# PwrSplit.net
KiCad netlist of a schematic drawn in EAGLE
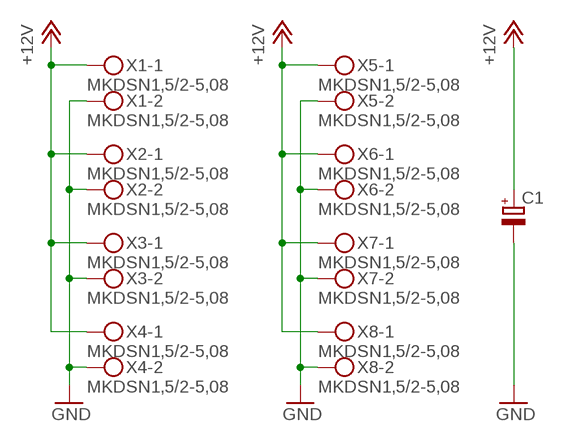
[diagram p0: schematic, sheet 1]

(export (version "E")
  (design (tool "Eeschema 10.0.6"))
  (components
    (comp (ref "C1")
      (value "ECAP")
      (footprint "eagle-import:E5-13")
      (libsource (lib "eagle-import") (part "ECAP"))
    )
    (comp (ref "X1")
      (value "MKDSN1,5/2-5,08")
      (footprint "eagle-import:MKDSN1,5_2-5,08")
      (libsource (lib "eagle-import") (part "MKDSN1,5/2-5,08"))
    )
    (comp (ref "X2")
      (value "MKDSN1,5/2-5,08")
      (footprint "eagle-import:MKDSN1,5_2-5,08")
      (libsource (lib "eagle-import") (part "MKDSN1,5/2-5,08"))
    )
    (comp (ref "X3")
      (value "MKDSN1,5/2-5,08")
      (footprint "eagle-import:MKDSN1,5_2-5,08")
      (libsource (lib "eagle-import") (part "MKDSN1,5/2-5,08"))
    )
    (comp (ref "X4")
      (value "MKDSN1,5/2-5,08")
      (footprint "eagle-import:MKDSN1,5_2-5,08")
      (libsource (lib "eagle-import") (part "MKDSN1,5/2-5,08"))
    )
    (comp (ref "X5")
      (value "MKDSN1,5/2-5,08")
      (footprint "eagle-import:MKDSN1,5_2-5,08")
      (libsource (lib "eagle-import") (part "MKDSN1,5/2-5,08"))
    )
    (comp (ref "X6")
      (value "MKDSN1,5/2-5,08")
      (footprint "eagle-import:MKDSN1,5_2-5,08")
      (libsource (lib "eagle-import") (part "MKDSN1,5/2-5,08"))
    )
    (comp (ref "X7")
      (value "MKDSN1,5/2-5,08")
      (footprint "eagle-import:MKDSN1,5_2-5,08")
      (libsource (lib "eagle-import") (part "MKDSN1,5/2-5,08"))
    )
    (comp (ref "X8")
      (value "MKDSN1,5/2-5,08")
      (footprint "eagle-import:MKDSN1,5_2-5,08")
      (libsource (lib "eagle-import") (part "MKDSN1,5/2-5,08"))
    )
  )
  (nets
    (net (code "1") (name "+12V") (class "Default")
      (node (ref "C1") (pin "+") (pinfunction "+_+") (pintype "passive"))
      (node (ref "X1") (pin "1") (pinfunction "KL_1") (pintype "passive"))
      (node (ref "X2") (pin "1") (pinfunction "KL_1") (pintype "passive"))
      (node (ref "X3") (pin "1") (pinfunction "KL_1") (pintype "passive"))
      (node (ref "X4") (pin "1") (pinfunction "KL_1") (pintype "passive"))
      (node (ref "X5") (pin "1") (pinfunction "KL_1") (pintype "passive"))
      (node (ref "X6") (pin "1") (pinfunction "KL_1") (pintype "passive"))
      (node (ref "X7") (pin "1") (pinfunction "KL_1") (pintype "passive"))
      (node (ref "X8") (pin "1") (pinfunction "KL_1") (pintype "passive"))
    )
    (net (code "2") (name "GND") (class "Default")
      (node (ref "C1") (pin "-") (pinfunction "-_-") (pintype "passive"))
      (node (ref "X1") (pin "2") (pinfunction "KL_2") (pintype "passive"))
      (node (ref "X2") (pin "2") (pinfunction "KL_2") (pintype "passive"))
      (node (ref "X3") (pin "2") (pinfunction "KL_2") (pintype "passive"))
      (node (ref "X4") (pin "2") (pinfunction "KL_2") (pintype "passive"))
      (node (ref "X5") (pin "2") (pinfunction "KL_2") (pintype "passive"))
      (node (ref "X6") (pin "2") (pinfunction "KL_2") (pintype "passive"))
      (node (ref "X7") (pin "2") (pinfunction "KL_2") (pintype "passive"))
      (node (ref "X8") (pin "2") (pinfunction "KL_2") (pintype "passive"))
    )
  )
)
